# queso_dip_v4_3.net
KiCad netlist of a schematic drawn in EAGLE
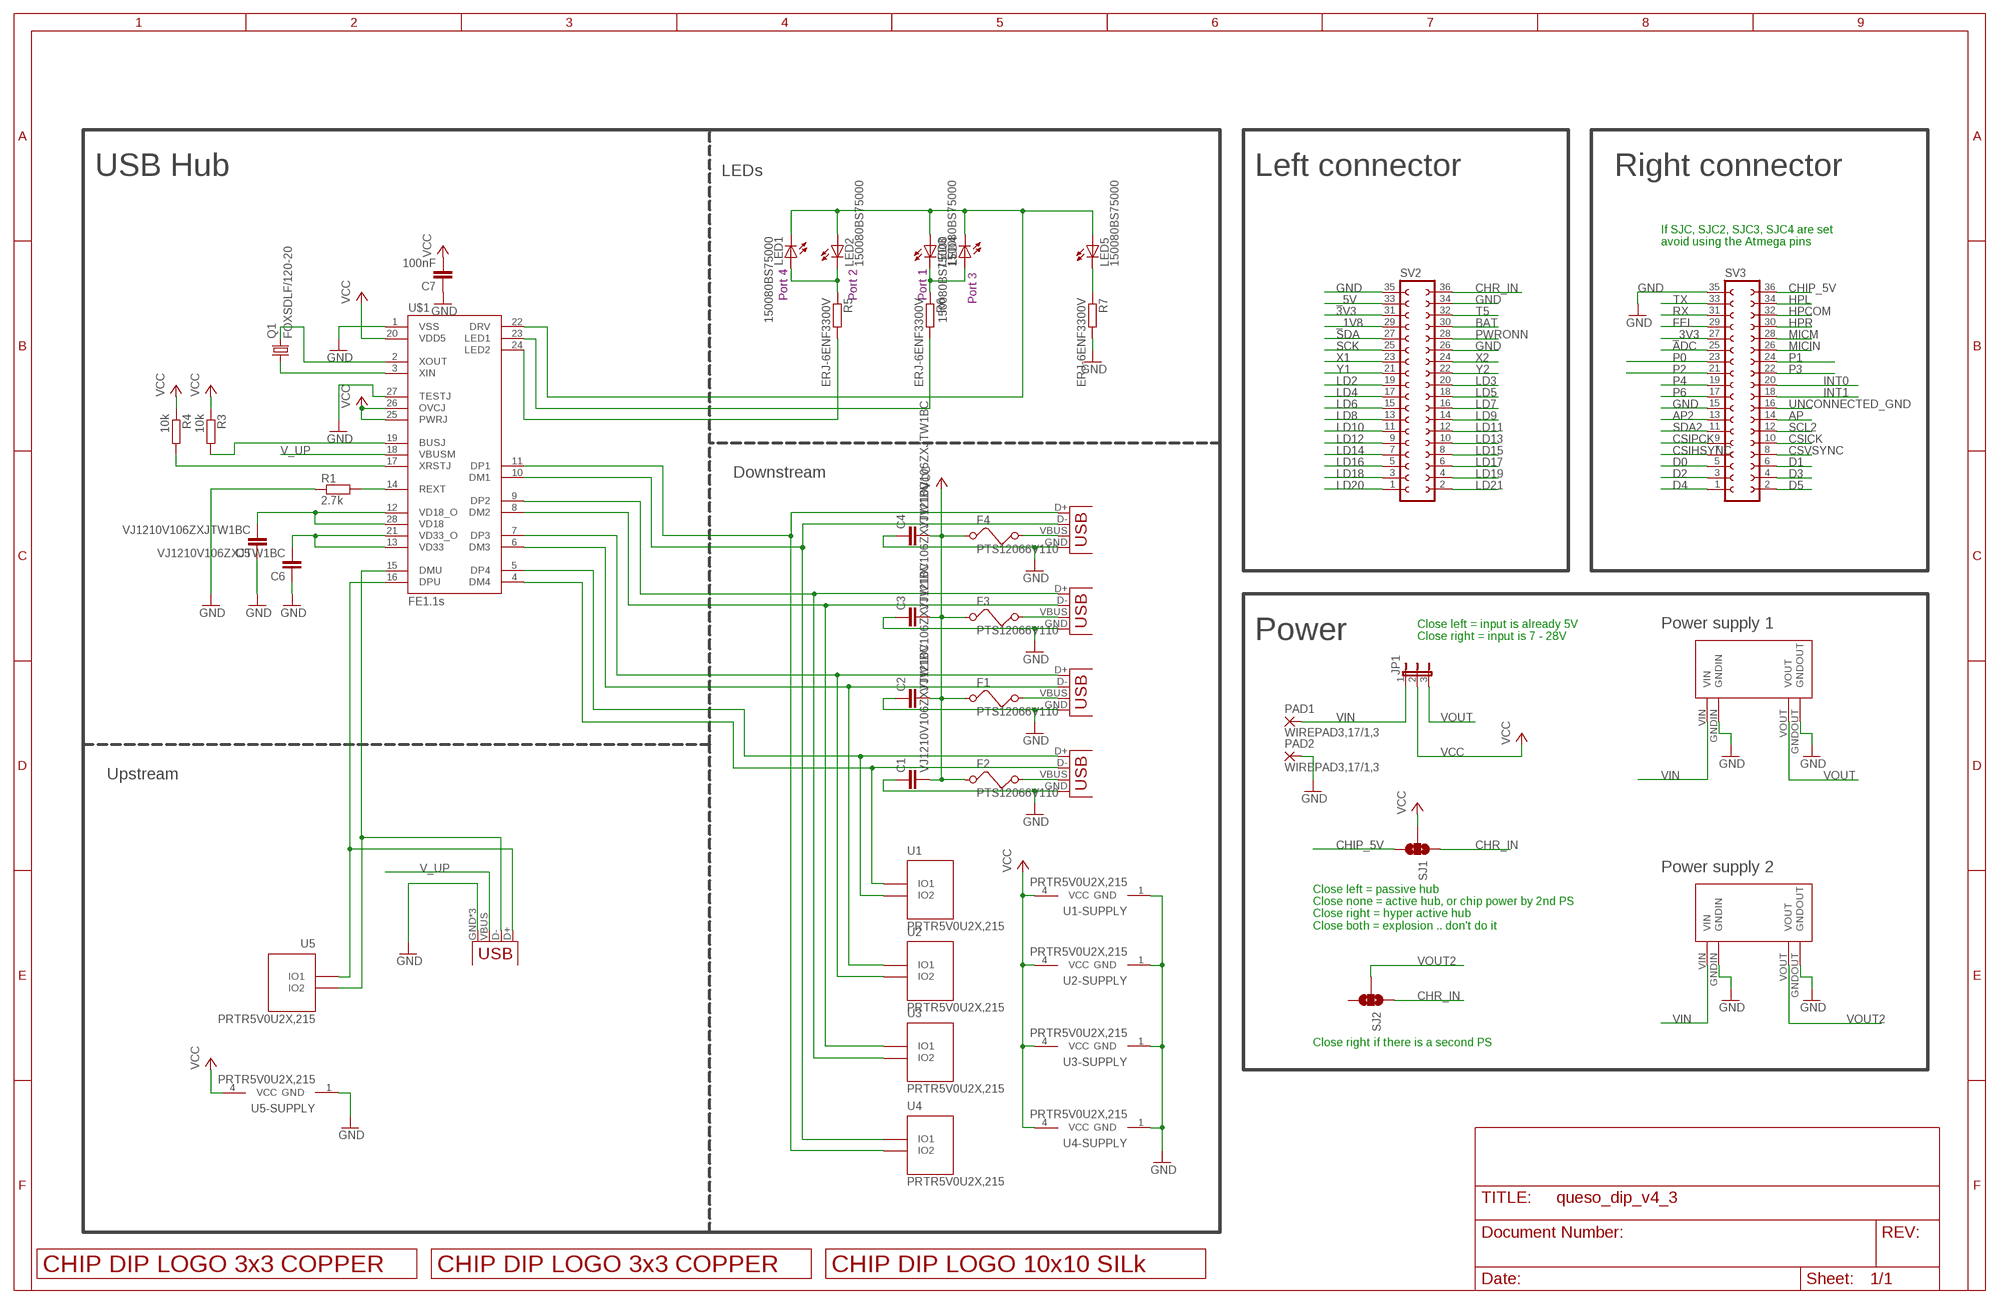
[diagram p0: schematic, sheet 1]

(export (version "E")
  (design (tool "Eeschema 10.0.6"))
  (components
    (comp (ref "C1")
      (value "VJ1210V106ZXJTW1BC")
      (footprint "eagle-import:C1210")
      (libsource (lib "eagle-import") (part "C-EUC1210"))
    )
    (comp (ref "C2")
      (value "VJ1210V106ZXJTW1BC")
      (footprint "eagle-import:C1210")
      (libsource (lib "eagle-import") (part "C-EUC1210"))
    )
    (comp (ref "C3")
      (value "VJ1210V106ZXJTW1BC")
      (footprint "eagle-import:C1210")
      (libsource (lib "eagle-import") (part "C-EUC1210"))
    )
    (comp (ref "C4")
      (value "VJ1210V106ZXJTW1BC")
      (footprint "eagle-import:C1210")
      (libsource (lib "eagle-import") (part "C-EUC1210"))
    )
    (comp (ref "C5")
      (value "VJ1210V106ZXJTW1BC")
      (footprint "eagle-import:C1210")
      (libsource (lib "eagle-import") (part "C-EUC1210"))
    )
    (comp (ref "C6")
      (value "VJ1210V106ZXJTW1BC")
      (footprint "eagle-import:C1210")
      (libsource (lib "eagle-import") (part "C-EUC1210"))
    )
    (comp (ref "C7")
      (value "100nF")
      (footprint "eagle-import:C0805")
      (libsource (lib "eagle-import") (part "C-EUC0805"))
    )
    (comp (ref "F1")
      (value "PTS12066V110")
      (footprint "eagle-import:1210")
      (libsource (lib "eagle-import") (part "FUSED"))
    )
    (comp (ref "F2")
      (value "PTS12066V110")
      (footprint "eagle-import:1210")
      (libsource (lib "eagle-import") (part "FUSED"))
    )
    (comp (ref "F3")
      (value "PTS12066V110")
      (footprint "eagle-import:1210")
      (libsource (lib "eagle-import") (part "FUSED"))
    )
    (comp (ref "F4")
      (value "PTS12066V110")
      (footprint "eagle-import:1210")
      (libsource (lib "eagle-import") (part "FUSED"))
    )
    (comp (ref "JP1")
      (value "JP2E")
      (footprint "eagle-import:JP2")
      (libsource (lib "eagle-import") (part "JP2E"))
    )
    (comp (ref "LED1")
      (value "150080BS75000")
      (footprint "eagle-import:CHIP-LED0805")
      (libsource (lib "eagle-import") (part "LEDCHIP-LED0805"))
    )
    (comp (ref "LED2")
      (value "150080BS75000")
      (footprint "eagle-import:CHIP-LED0805")
      (libsource (lib "eagle-import") (part "LEDCHIP-LED0805"))
    )
    (comp (ref "LED3")
      (value "150080BS75000")
      (footprint "eagle-import:CHIP-LED0805")
      (libsource (lib "eagle-import") (part "LEDCHIP-LED0805"))
    )
    (comp (ref "LED4")
      (value "150080BS75000")
      (footprint "eagle-import:CHIP-LED0805")
      (libsource (lib "eagle-import") (part "LEDCHIP-LED0805"))
    )
    (comp (ref "LED5")
      (value "150080BS75000")
      (footprint "eagle-import:CHIP-LED0805")
      (libsource (lib "eagle-import") (part "LEDCHIP-LED0805"))
    )
    (comp (ref "PAD1")
      (value "WIREPAD3,17/1,3")
      (footprint "eagle-import:3,17_1,3")
      (libsource (lib "eagle-import") (part "WIREPAD3,17/1,3"))
    )
    (comp (ref "PAD2")
      (value "WIREPAD3,17/1,3")
      (footprint "eagle-import:3,17_1,3")
      (libsource (lib "eagle-import") (part "WIREPAD3,17/1,3"))
    )
    (comp (ref "Q1")
      (value "FOXSDLF/120-20")
      (footprint "eagle-import:SM49")
      (libsource (lib "eagle-import") (part "CRYSTALSM49"))
    )
    (comp (ref "R1")
      (value "2.7k")
      (footprint "eagle-import:R0805")
      (libsource (lib "eagle-import") (part "R-EU_R0805"))
    )
    (comp (ref "R3")
      (value "10k")
      (footprint "eagle-import:R0805")
      (libsource (lib "eagle-import") (part "R-EU_R0805"))
    )
    (comp (ref "R4")
      (value "10k")
      (footprint "eagle-import:R0805")
      (libsource (lib "eagle-import") (part "R-EU_R0805"))
    )
    (comp (ref "R5")
      (value "ERJ-6ENF3300V")
      (footprint "eagle-import:R0805")
      (libsource (lib "eagle-import") (part "R-EU_R0805"))
    )
    (comp (ref "R6")
      (value "ERJ-6ENF3300V")
      (footprint "eagle-import:R0805")
      (libsource (lib "eagle-import") (part "R-EU_R0805"))
    )
    (comp (ref "R7")
      (value "ERJ-6ENF3300V")
      (footprint "eagle-import:R0805")
      (libsource (lib "eagle-import") (part "R-EU_R0805"))
    )
    (comp (ref "SJ1")
      (value "SOLDERJUMPER_2WAYT")
      (footprint "eagle-import:SJ_2")
      (libsource (lib "eagle-import") (part "SOLDERJUMPER_2WAYT"))
    )
    (comp (ref "SJ2")
      (value "SOLDERJUMPER_2WAYT")
      (footprint "eagle-import:SJ_2")
      (libsource (lib "eagle-import") (part "SOLDERJUMPER_2WAYT"))
    )
    (comp (ref "SV2")
      (value "FE18-2")
      (footprint "eagle-import:FE18-2")
      (libsource (lib "eagle-import") (part "FE18-2"))
    )
    (comp (ref "SV3")
      (value "FE18-2")
      (footprint "eagle-import:FE18-2")
      (libsource (lib "eagle-import") (part "FE18-2"))
    )
    (comp (ref "U$1")
      (value "FE1.1S")
      (footprint "eagle-import:FE1.1S_SSOP-28")
      (libsource (lib "eagle-import") (part "FE1.1S"))
    )
    (comp (ref "U$2")
      (value "LOGO_3X3_COPPER")
      (footprint "eagle-import:LOGO_3X3_COPPER")
      (libsource (lib "eagle-import") (part "LOGO_3X3_COPPER"))
    )
    (comp (ref "U$3")
      (value "MP1584EN")
      (footprint "eagle-import:MP1584EN")
      (libsource (lib "eagle-import") (part "MP1584EN"))
    )
    (comp (ref "U$4")
      (value "LOGO_3X3_COPPER")
      (footprint "eagle-import:LOGO_3X3_COPPER")
      (libsource (lib "eagle-import") (part "LOGO_3X3_COPPER"))
    )
    (comp (ref "U$5")
      (value "LOGO_10X10_SILK")
      (footprint "eagle-import:LOGO_10X10_SILK")
      (libsource (lib "eagle-import") (part "LOGO_10X10_SILK"))
    )
    (comp (ref "U$9")
      (value "MP1584EN")
      (footprint "eagle-import:MP1584EN")
      (libsource (lib "eagle-import") (part "MP1584EN"))
    )
    (comp (ref "U1")
      (value "PRTR5V0U2X,215")
      (footprint "eagle-import:SOT-143B")
      (fields (field (name "MANUFACTURER") "NXP Semiconductors"))
      (libsource (lib "eagle-import") (part "PRTR5V0U2X?"))
    )
    (comp (ref "U2")
      (value "PRTR5V0U2X,215")
      (footprint "eagle-import:SOT-143B")
      (fields (field (name "MANUFACTURER") "NXP Semiconductors"))
      (libsource (lib "eagle-import") (part "PRTR5V0U2X?"))
    )
    (comp (ref "U3")
      (value "PRTR5V0U2X,215")
      (footprint "eagle-import:SOT-143B")
      (fields (field (name "MANUFACTURER") "NXP Semiconductors"))
      (libsource (lib "eagle-import") (part "PRTR5V0U2X?"))
    )
    (comp (ref "U4")
      (value "PRTR5V0U2X,215")
      (footprint "eagle-import:SOT-143B")
      (fields (field (name "MANUFACTURER") "NXP Semiconductors"))
      (libsource (lib "eagle-import") (part "PRTR5V0U2X?"))
    )
    (comp (ref "U5")
      (value "PRTR5V0U2X,215")
      (footprint "eagle-import:SOT-143B")
      (fields (field (name "MANUFACTURER") "NXP Semiconductors"))
      (libsource (lib "eagle-import") (part "PRTR5V0U2X?"))
    )
    (comp (ref "USB")
      (value "USBUSB-MICROB-SMT-DIP")
      (footprint "eagle-import:USB-MICROB-SMT-DIP")
      (libsource (lib "eagle-import") (part "USBUSB-MICROB-SMT-DIP"))
    )
    (comp (ref "X1")
      (value "USB-A-HU")
      (footprint "eagle-import:USB-A-HU")
      (libsource (lib "eagle-import") (part "USB-A-HU"))
    )
    (comp (ref "X2")
      (value "USB-A-HU")
      (footprint "eagle-import:USB-A-HU")
      (libsource (lib "eagle-import") (part "USB-A-HU"))
    )
    (comp (ref "X3")
      (value "USB-A-HU")
      (footprint "eagle-import:USB-A-HU")
      (libsource (lib "eagle-import") (part "USB-A-HU"))
    )
    (comp (ref "X4")
      (value "USB-A-HU")
      (footprint "eagle-import:USB-A-HU")
      (libsource (lib "eagle-import") (part "USB-A-HU"))
    )
  )
  (nets
    (net (code "1") (name "/3V3") (class "Default")
      (node (ref "SV2") (pin "31") (pinfunction "31_31") (pintype "passive"))
    )
    (net (code "2") (name "/ADC") (class "Default")
      (node (ref "SV3") (pin "25") (pinfunction "25_25") (pintype "passive"))
    )
    (net (code "3") (name "/AP") (class "Default")
      (node (ref "SV3") (pin "14") (pinfunction "14_14") (pintype "passive"))
    )
    (net (code "4") (name "/AP2") (class "Default")
      (node (ref "SV3") (pin "13") (pinfunction "13_13") (pintype "passive"))
    )
    (net (code "5") (name "/BAT") (class "Default")
      (node (ref "SV2") (pin "30") (pinfunction "30_30") (pintype "passive"))
    )
    (net (code "6") (name "/CHIP_5V") (class "Default")
      (node (ref "SJ1") (pin "3") (pinfunction "3_3") (pintype "passive"))
      (node (ref "SV3") (pin "36") (pinfunction "36_36") (pintype "passive"))
    )
    (net (code "7") (name "/CHR_IN") (class "Default")
      (node (ref "SJ1") (pin "1") (pinfunction "1_1") (pintype "passive"))
      (node (ref "SJ2") (pin "1") (pinfunction "1_1") (pintype "passive"))
      (node (ref "SV2") (pin "36") (pinfunction "36_36") (pintype "passive"))
    )
    (net (code "8") (name "/CSICK") (class "Default")
      (node (ref "SV3") (pin "10") (pinfunction "10_10") (pintype "passive"))
    )
    (net (code "9") (name "/CSIHSYNC") (class "Default")
      (node (ref "SV3") (pin "7") (pinfunction "7_7") (pintype "passive"))
    )
    (net (code "10") (name "/CSIPCK") (class "Default")
      (node (ref "SV3") (pin "9") (pinfunction "9_9") (pintype "passive"))
    )
    (net (code "11") (name "/CSVSYNC") (class "Default")
      (node (ref "SV3") (pin "8") (pinfunction "8_8") (pintype "passive"))
    )
    (net (code "12") (name "/D0") (class "Default")
      (node (ref "SV3") (pin "5") (pinfunction "5_5") (pintype "passive"))
    )
    (net (code "13") (name "/D1") (class "Default")
      (node (ref "SV3") (pin "6") (pinfunction "6_6") (pintype "passive"))
    )
    (net (code "14") (name "/D2") (class "Default")
      (node (ref "SV3") (pin "3") (pinfunction "3_3") (pintype "passive"))
    )
    (net (code "15") (name "/D3") (class "Default")
      (node (ref "SV3") (pin "4") (pinfunction "4_4") (pintype "passive"))
    )
    (net (code "16") (name "/D4") (class "Default")
      (node (ref "SV3") (pin "1") (pinfunction "1_1") (pintype "passive"))
    )
    (net (code "17") (name "/D5") (class "Default")
      (node (ref "SV3") (pin "2") (pinfunction "2_2") (pintype "passive"))
    )
    (net (code "18") (name "/FEL") (class "Default")
      (node (ref "SV3") (pin "29") (pinfunction "29_29") (pintype "passive"))
    )
    (net (code "19") (name "/HPCOM") (class "Default")
      (node (ref "SV3") (pin "32") (pinfunction "32_32") (pintype "passive"))
    )
    (net (code "20") (name "/HPL") (class "Default")
      (node (ref "SV3") (pin "34") (pinfunction "34_34") (pintype "passive"))
    )
    (net (code "21") (name "/HPR") (class "Default")
      (node (ref "SV3") (pin "30") (pinfunction "30_30") (pintype "passive"))
    )
    (net (code "22") (name "/INT0") (class "Default")
      (node (ref "SV3") (pin "20") (pinfunction "20_20") (pintype "passive"))
    )
    (net (code "23") (name "/INT1") (class "Default")
      (node (ref "SV3") (pin "18") (pinfunction "18_18") (pintype "passive"))
    )
    (net (code "24") (name "/LD2") (class "Default")
      (node (ref "SV2") (pin "19") (pinfunction "19_19") (pintype "passive"))
    )
    (net (code "25") (name "/LD3") (class "Default")
      (node (ref "SV2") (pin "20") (pinfunction "20_20") (pintype "passive"))
    )
    (net (code "26") (name "/LD4") (class "Default")
      (node (ref "SV2") (pin "17") (pinfunction "17_17") (pintype "passive"))
    )
    (net (code "27") (name "/LD5") (class "Default")
      (node (ref "SV2") (pin "18") (pinfunction "18_18") (pintype "passive"))
    )
    (net (code "28") (name "/LD6") (class "Default")
      (node (ref "SV2") (pin "15") (pinfunction "15_15") (pintype "passive"))
    )
    (net (code "29") (name "/LD7") (class "Default")
      (node (ref "SV2") (pin "16") (pinfunction "16_16") (pintype "passive"))
    )
    (net (code "30") (name "/LD8") (class "Default")
      (node (ref "SV2") (pin "13") (pinfunction "13_13") (pintype "passive"))
    )
    (net (code "31") (name "/LD9") (class "Default")
      (node (ref "SV2") (pin "14") (pinfunction "14_14") (pintype "passive"))
    )
    (net (code "32") (name "/LD10") (class "Default")
      (node (ref "SV2") (pin "11") (pinfunction "11_11") (pintype "passive"))
    )
    (net (code "33") (name "/LD11") (class "Default")
      (node (ref "SV2") (pin "12") (pinfunction "12_12") (pintype "passive"))
    )
    (net (code "34") (name "/LD12") (class "Default")
      (node (ref "SV2") (pin "9") (pinfunction "9_9") (pintype "passive"))
    )
    (net (code "35") (name "/LD13") (class "Default")
      (node (ref "SV2") (pin "10") (pinfunction "10_10") (pintype "passive"))
    )
    (net (code "36") (name "/LD14") (class "Default")
      (node (ref "SV2") (pin "7") (pinfunction "7_7") (pintype "passive"))
    )
    (net (code "37") (name "/LD15") (class "Default")
      (node (ref "SV2") (pin "8") (pinfunction "8_8") (pintype "passive"))
    )
    (net (code "38") (name "/LD16") (class "Default")
      (node (ref "SV2") (pin "5") (pinfunction "5_5") (pintype "passive"))
    )
    (net (code "39") (name "/LD17") (class "Default")
      (node (ref "SV2") (pin "6") (pinfunction "6_6") (pintype "passive"))
    )
    (net (code "40") (name "/LD18") (class "Default")
      (node (ref "SV2") (pin "3") (pinfunction "3_3") (pintype "passive"))
    )
    (net (code "41") (name "/LD19") (class "Default")
      (node (ref "SV2") (pin "4") (pinfunction "4_4") (pintype "passive"))
    )
    (net (code "42") (name "/LD20") (class "Default")
      (node (ref "SV2") (pin "1") (pinfunction "1_1") (pintype "passive"))
    )
    (net (code "43") (name "/LD21") (class "Default")
      (node (ref "SV2") (pin "2") (pinfunction "2_2") (pintype "passive"))
    )
    (net (code "44") (name "/MICIN") (class "Default")
      (node (ref "SV3") (pin "26") (pinfunction "26_26") (pintype "passive"))
    )
    (net (code "45") (name "/MICM") (class "Default")
      (node (ref "SV3") (pin "28") (pinfunction "28_28") (pintype "passive"))
    )
    (net (code "46") (name "/P0") (class "Default")
      (node (ref "SV3") (pin "23") (pinfunction "23_23") (pintype "passive"))
    )
    (net (code "47") (name "/P1") (class "Default")
      (node (ref "SV3") (pin "24") (pinfunction "24_24") (pintype "passive"))
    )
    (net (code "48") (name "/P2") (class "Default")
      (node (ref "SV3") (pin "21") (pinfunction "21_21") (pintype "passive"))
    )
    (net (code "49") (name "/P3") (class "Default")
      (node (ref "SV3") (pin "22") (pinfunction "22_22") (pintype "passive"))
    )
    (net (code "50") (name "/P4") (class "Default")
      (node (ref "SV3") (pin "19") (pinfunction "19_19") (pintype "passive"))
    )
    (net (code "51") (name "/P6") (class "Default")
      (node (ref "SV3") (pin "17") (pinfunction "17_17") (pintype "passive"))
    )
    (net (code "52") (name "/PWRONN") (class "Default")
      (node (ref "SV2") (pin "28") (pinfunction "28_28") (pintype "passive"))
    )
    (net (code "53") (name "/RX") (class "Default")
      (node (ref "SV3") (pin "31") (pinfunction "31_31") (pintype "passive"))
    )
    (net (code "54") (name "/SCK") (class "Default")
      (node (ref "SV2") (pin "25") (pinfunction "25_25") (pintype "passive"))
    )
    (net (code "55") (name "/SCL2") (class "Default")
      (node (ref "SV3") (pin "12") (pinfunction "12_12") (pintype "passive"))
    )
    (net (code "56") (name "/SDA") (class "Default")
      (node (ref "SV2") (pin "27") (pinfunction "27_27") (pintype "passive"))
    )
    (net (code "57") (name "/SDA2") (class "Default")
      (node (ref "SV3") (pin "11") (pinfunction "11_11") (pintype "passive"))
    )
    (net (code "58") (name "/T5") (class "Default")
      (node (ref "SV2") (pin "32") (pinfunction "32_32") (pintype "passive"))
    )
    (net (code "59") (name "/TX") (class "Default")
      (node (ref "SV3") (pin "33") (pinfunction "33_33") (pintype "passive"))
    )
    (net (code "60") (name "/UNCONNECTED_GND") (class "Default")
      (node (ref "SV3") (pin "16") (pinfunction "16_16") (pintype "passive"))
    )
    (net (code "61") (name "/VIN") (class "Default")
      (node (ref "JP1") (pin "1") (pinfunction "1_1") (pintype "passive"))
      (node (ref "PAD1") (pin "1") (pinfunction "P_1") (pintype "passive"))
      (node (ref "U$3") (pin "VIN") (pinfunction "VIN_VIN") (pintype "power_in"))
      (node (ref "U$9") (pin "VIN") (pinfunction "VIN_VIN") (pintype "power_in"))
    )
    (net (code "62") (name "/VOUT") (class "Default")
      (node (ref "JP1") (pin "3") (pinfunction "3_3") (pintype "passive"))
      (node (ref "U$9") (pin "VOUT") (pinfunction "VOUT_VOUT") (pintype "power_in"))
    )
    (net (code "63") (name "/VOUT2") (class "Default")
      (node (ref "SJ2") (pin "2") (pinfunction "2_2") (pintype "passive"))
      (node (ref "U$3") (pin "VOUT") (pinfunction "VOUT_VOUT") (pintype "power_in"))
    )
    (net (code "64") (name "/V_UP") (class "Default")
      (node (ref "U$1") (pin "18") (pinfunction "VBUSM_18") (pintype "bidirectional"))
      (node (ref "USB") (pin "VBUS") (pinfunction "VBUS_VBUS") (pintype "bidirectional"))
    )
    (net (code "65") (name "/X1") (class "Default")
      (node (ref "SV2") (pin "23") (pinfunction "23_23") (pintype "passive"))
    )
    (net (code "66") (name "/X2") (class "Default")
      (node (ref "SV2") (pin "24") (pinfunction "24_24") (pintype "passive"))
    )
    (net (code "67") (name "/Y1") (class "Default")
      (node (ref "SV2") (pin "21") (pinfunction "21_21") (pintype "passive"))
    )
    (net (code "68") (name "/Y2") (class "Default")
      (node (ref "SV2") (pin "22") (pinfunction "22_22") (pintype "passive"))
    )
    (net (code "69") (name "/_1V8") (class "Default")
      (node (ref "SV2") (pin "29") (pinfunction "29_29") (pintype "passive"))
    )
    (net (code "70") (name "/_3V3") (class "Default")
      (node (ref "SV3") (pin "27") (pinfunction "27_27") (pintype "passive"))
    )
    (net (code "71") (name "/_5V") (class "Default")
      (node (ref "SV2") (pin "33") (pinfunction "33_33") (pintype "passive"))
    )
    (net (code "72") (name "GND") (class "Default")
      (node (ref "C1") (pin "1") (pinfunction "1_1") (pintype "passive"))
      (node (ref "C2") (pin "1") (pinfunction "1_1") (pintype "passive"))
      (node (ref "C3") (pin "1") (pinfunction "1_1") (pintype "passive"))
      (node (ref "C4") (pin "1") (pinfunction "1_1") (pintype "passive"))
      (node (ref "C5") (pin "1") (pinfunction "1_1") (pintype "passive"))
      (node (ref "C6") (pin "1") (pinfunction "1_1") (pintype "passive"))
      (node (ref "C7") (pin "1") (pinfunction "1_1") (pintype "passive"))
      (node (ref "PAD2") (pin "1") (pinfunction "P_1") (pintype "passive"))
      (node (ref "R1") (pin "1") (pinfunction "1_1") (pintype "passive"))
      (node (ref "R7") (pin "2") (pinfunction "2_2") (pintype "passive"))
      (node (ref "SV2") (pin "26") (pinfunction "26_26") (pintype "passive"))
      (node (ref "SV2") (pin "34") (pinfunction "34_34") (pintype "passive"))
      (node (ref "SV2") (pin "35") (pinfunction "35_35") (pintype "passive"))
      (node (ref "SV3") (pin "15") (pinfunction "15_15") (pintype "passive"))
      (node (ref "SV3") (pin "35") (pinfunction "35_35") (pintype "passive"))
      (node (ref "U$1") (pin "1") (pinfunction "VSS_1") (pintype "bidirectional"))
      (node (ref "U$1") (pin "27") (pinfunction "TESTJ_27") (pintype "bidirectional"))
      (node (ref "U$3") (pin "GNDIN") (pinfunction "GNDIN_GNDIN") (pintype "power_in"))
      (node (ref "U$3") (pin "GNDOUT") (pinfunction "GNDOUT_GNDOUT") (pintype "power_in"))
      (node (ref "U$9") (pin "GNDIN") (pinfunction "GNDIN_GNDIN") (pintype "power_in"))
      (node (ref "U$9") (pin "GNDOUT") (pinfunction "GNDOUT_GNDOUT") (pintype "power_in"))
      (node (ref "U1") (pin "1") (pinfunction "GND_1") (pintype "bidirectional"))
      (node (ref "U2") (pin "1") (pinfunction "GND_1") (pintype "bidirectional"))
      (node (ref "U3") (pin "1") (pinfunction "GND_1") (pintype "bidirectional"))
      (node (ref "U4") (pin "1") (pinfunction "GND_1") (pintype "bidirectional"))
      (node (ref "U5") (pin "1") (pinfunction "GND_1") (pintype "bidirectional"))
      (node (ref "USB") (pin "GND") (pinfunction "GND_GND") (pintype "bidirectional"))
      (node (ref "USB") (pin "MT1") (pinfunction "GND_MT1") (pintype "bidirectional"))
      (node (ref "USB") (pin "MT2") (pinfunction "GND_MT2") (pintype "bidirectional"))
      (node (ref "X1") (pin "GND") (pinfunction "GND_GND") (pintype "bidirectional"))
      (node (ref "X2") (pin "GND") (pinfunction "GND_GND") (pintype "bidirectional"))
      (node (ref "X3") (pin "GND") (pinfunction "GND_GND") (pintype "bidirectional"))
      (node (ref "X4") (pin "GND") (pinfunction "GND_GND") (pintype "bidirectional"))
    )
    (net (code "73") (name "Net-(F1-Pad2)") (class "Default")
      (node (ref "F1") (pin "2") (pinfunction "2_2") (pintype "passive"))
      (node (ref "X2") (pin "VBUS") (pinfunction "VBUS_VBUS") (pintype "bidirectional"))
    )
    (net (code "74") (name "Net-(F2-Pad2)") (class "Default")
      (node (ref "F2") (pin "2") (pinfunction "2_2") (pintype "passive"))
      (node (ref "X1") (pin "VBUS") (pinfunction "VBUS_VBUS") (pintype "bidirectional"))
    )
    (net (code "75") (name "Net-(F3-Pad2)") (class "Default")
      (node (ref "F3") (pin "2") (pinfunction "2_2") (pintype "passive"))
      (node (ref "X3") (pin "VBUS") (pinfunction "VBUS_VBUS") (pintype "bidirectional"))
    )
    (net (code "76") (name "Net-(F4-Pad2)") (class "Default")
      (node (ref "F4") (pin "2") (pinfunction "2_2") (pintype "passive"))
      (node (ref "X4") (pin "VBUS") (pinfunction "VBUS_VBUS") (pintype "bidirectional"))
    )
    (net (code "77") (name "Net-(LED1-PadA)") (class "Default")
      (node (ref "LED1") (pin "A") (pinfunction "A_A") (pintype "passive"))
      (node (ref "LED2") (pin "C") (pinfunction "C_C") (pintype "passive"))
      (node (ref "R5") (pin "1") (pinfunction "1_1") (pintype "passive"))
    )
    (net (code "78") (name "Net-(LED3-PadC)") (class "Default")
      (node (ref "LED3") (pin "C") (pinfunction "C_C") (pintype "passive"))
      (node (ref "LED4") (pin "A") (pinfunction "A_A") (pintype "passive"))
      (node (ref "R6") (pin "1") (pinfunction "1_1") (pintype "passive"))
    )
    (net (code "79") (name "Net-(LED5-PadC)") (class "Default")
      (node (ref "LED5") (pin "C") (pinfunction "C_C") (pintype "passive"))
      (node (ref "R7") (pin "1") (pinfunction "1_1") (pintype "passive"))
    )
    (net (code "80") (name "Net-(U$1-BUSJ)") (class "Default")
      (node (ref "R3") (pin "2") (pinfunction "2_2") (pintype "passive"))
      (node (ref "U$1") (pin "19") (pinfunction "BUSJ_19") (pintype "bidirectional"))
    )
    (net (code "81") (name "Net-(U$1-DM1)") (class "Default")
      (node (ref "U$1") (pin "10") (pinfunction "DM1_10") (pintype "bidirectional"))
      (node (ref "U4") (pin "2") (pinfunction "IO1_2") (pintype "bidirectional"))
      (node (ref "X4") (pin "D-") (pinfunction "D-_D-") (pintype "bidirectional"))
    )
    (net (code "82") (name "Net-(U$1-DM2)") (class "Default")
      (node (ref "U$1") (pin "8") (pinfunction "DM2_8") (pintype "bidirectional"))
      (node (ref "U3") (pin "2") (pinfunction "IO1_2") (pintype "bidirectional"))
      (node (ref "X3") (pin "D-") (pinfunction "D-_D-") (pintype "bidirectional"))
    )
    (net (code "83") (name "Net-(U$1-DM3)") (class "Default")
      (node (ref "U$1") (pin "6") (pinfunction "DM3_6") (pintype "bidirectional"))
      (node (ref "U2") (pin "2") (pinfunction "IO1_2") (pintype "bidirectional"))
      (node (ref "X2") (pin "D-") (pinfunction "D-_D-") (pintype "bidirectional"))
    )
    (net (code "84") (name "Net-(U$1-DM4)") (class "Default")
      (node (ref "U$1") (pin "4") (pinfunction "DM4_4") (pintype "bidirectional"))
      (node (ref "U1") (pin "2") (pinfunction "IO1_2") (pintype "bidirectional"))
      (node (ref "X1") (pin "D-") (pinfunction "D-_D-") (pintype "bidirectional"))
    )
    (net (code "85") (name "Net-(U$1-DMU)") (class "Default")
      (node (ref "U$1") (pin "15") (pinfunction "DMU_15") (pintype "bidirectional"))
      (node (ref "U5") (pin "3") (pinfunction "IO2_3") (pintype "bidirectional"))
      (node (ref "USB") (pin "D-") (pinfunction "D-_D-") (pintype "bidirectional"))
    )
    (net (code "86") (name "Net-(U$1-DP1)") (class "Default")
      (node (ref "U$1") (pin "11") (pinfunction "DP1_11") (pintype "bidirectional"))
      (node (ref "U4") (pin "3") (pinfunction "IO2_3") (pintype "bidirectional"))
      (node (ref "X4") (pin "D+") (pinfunction "D+_D+") (pintype "bidirectional"))
    )
    (net (code "87") (name "Net-(U$1-DP2)") (class "Default")
      (node (ref "U$1") (pin "9") (pinfunction "DP2_9") (pintype "bidirectional"))
      (node (ref "U3") (pin "3") (pinfunction "IO2_3") (pintype "bidirectional"))
      (node (ref "X3") (pin "D+") (pinfunction "D+_D+") (pintype "bidirectional"))
    )
    (net (code "88") (name "Net-(U$1-DP3)") (class "Default")
      (node (ref "U$1") (pin "7") (pinfunction "DP3_7") (pintype "bidirectional"))
      (node (ref "U2") (pin "3") (pinfunction "IO2_3") (pintype "bidirectional"))
      (node (ref "X2") (pin "D+") (pinfunction "D+_D+") (pintype "bidirectional"))
    )
    (net (code "89") (name "Net-(U$1-DP4)") (class "Default")
      (node (ref "U$1") (pin "5") (pinfunction "DP4_5") (pintype "bidirectional"))
      (node (ref "U1") (pin "3") (pinfunction "IO2_3") (pintype "bidirectional"))
      (node (ref "X1") (pin "D+") (pinfunction "D+_D+") (pintype "bidirectional"))
    )
    (net (code "90") (name "Net-(U$1-DPU)") (class "Default")
      (node (ref "U$1") (pin "16") (pinfunction "DPU_16") (pintype "bidirectional"))
      (node (ref "U5") (pin "2") (pinfunction "IO1_2") (pintype "bidirectional"))
      (node (ref "USB") (pin "D+") (pinfunction "D+_D+") (pintype "bidirectional"))
    )
    (net (code "91") (name "Net-(U$1-DRV)") (class "Default")
      (node (ref "LED1") (pin "C") (pinfunction "C_C") (pintype "passive"))
      (node (ref "LED2") (pin "A") (pinfunction "A_A") (pintype "passive"))
      (node (ref "LED3") (pin "A") (pinfunction "A_A") (pintype "passive"))
      (node (ref "LED4") (pin "C") (pinfunction "C_C") (pintype "passive"))
      (node (ref "LED5") (pin "A") (pinfunction "A_A") (pintype "passive"))
      (node (ref "U$1") (pin "22") (pinfunction "DRV_22") (pintype "bidirectional"))
    )
    (net (code "92") (name "Net-(U$1-LED1)") (class "Default")
      (node (ref "R6") (pin "2") (pinfunction "2_2") (pintype "passive"))
      (node (ref "U$1") (pin "23") (pinfunction "LED1_23") (pintype "bidirectional"))
    )
    (net (code "93") (name "Net-(U$1-LED2)") (class "Default")
      (node (ref "R5") (pin "2") (pinfunction "2_2") (pintype "passive"))
      (node (ref "U$1") (pin "24") (pinfunction "LED2_24") (pintype "bidirectional"))
    )
    (net (code "94") (name "Net-(U$1-REXT)") (class "Default")
      (node (ref "R1") (pin "2") (pinfunction "2_2") (pintype "passive"))
      (node (ref "U$1") (pin "14") (pinfunction "REXT_14") (pintype "bidirectional"))
    )
    (net (code "95") (name "Net-(U$1-VD18)") (class "Default")
      (node (ref "C5") (pin "2") (pinfunction "2_2") (pintype "passive"))
      (node (ref "U$1") (pin "12") (pinfunction "VD18_O_12") (pintype "bidirectional"))
      (node (ref "U$1") (pin "28") (pinfunction "VD18_28") (pintype "bidirectional"))
    )
    (net (code "96") (name "Net-(U$1-VD33)") (class "Default")
      (node (ref "C6") (pin "2") (pinfunction "2_2") (pintype "passive"))
      (node (ref "U$1") (pin "13") (pinfunction "VD33_13") (pintype "bidirectional"))
      (node (ref "U$1") (pin "21") (pinfunction "VD33_O_21") (pintype "bidirectional"))
    )
    (net (code "97") (name "Net-(U$1-XIN)") (class "Default")
      (node (ref "Q1") (pin "1") (pinfunction "1_1") (pintype "passive"))
      (node (ref "U$1") (pin "3") (pinfunction "XIN_3") (pintype "bidirectional"))
    )
    (net (code "98") (name "Net-(U$1-XOUT)") (class "Default")
      (node (ref "Q1") (pin "2") (pinfunction "2_2") (pintype "passive"))
      (node (ref "U$1") (pin "2") (pinfunction "XOUT_2") (pintype "bidirectional"))
    )
    (net (code "99") (name "Net-(U$1-XRSTJ)") (class "Default")
      (node (ref "R4") (pin "2") (pinfunction "2_2") (pintype "passive"))
      (node (ref "U$1") (pin "17") (pinfunction "XRSTJ_17") (pintype "bidirectional"))
    )
    (net (code "100") (name "VCC") (class "Default")
      (node (ref "C1") (pin "2") (pinfunction "2_2") (pintype "passive"))
      (node (ref "C2") (pin "2") (pinfunction "2_2") (pintype "passive"))
      (node (ref "C3") (pin "2") (pinfunction "2_2") (pintype "passive"))
      (node (ref "C4") (pin "2") (pinfunction "2_2") (pintype "passive"))
      (node (ref "C7") (pin "2") (pinfunction "2_2") (pintype "passive"))
      (node (ref "F1") (pin "1") (pinfunction "1_1") (pintype "passive"))
      (node (ref "F2") (pin "1") (pinfunction "1_1") (pintype "passive"))
      (node (ref "F3") (pin "1") (pinfunction "1_1") (pintype "passive"))
      (node (ref "F4") (pin "1") (pinfunction "1_1") (pintype "passive"))
      (node (ref "JP1") (pin "2") (pinfunction "2_2") (pintype "passive"))
      (node (ref "R3") (pin "1") (pinfunction "1_1") (pintype "passive"))
      (node (ref "R4") (pin "1") (pinfunction "1_1") (pintype "passive"))
      (node (ref "SJ1") (pin "2") (pinfunction "2_2") (pintype "passive"))
      (node (ref "U$1") (pin "20") (pinfunction "VDD5_20") (pintype "bidirectional"))
      (node (ref "U$1") (pin "25") (pinfunction "PWRJ_25") (pintype "bidirectional"))
      (node (ref "U$1") (pin "26") (pinfunction "OVCJ_26") (pintype "bidirectional"))
      (node (ref "U1") (pin "4") (pinfunction "VCC_4") (pintype "bidirectional"))
      (node (ref "U2") (pin "4") (pinfunction "VCC_4") (pintype "bidirectional"))
      (node (ref "U3") (pin "4") (pinfunction "VCC_4") (pintype "bidirectional"))
      (node (ref "U4") (pin "4") (pinfunction "VCC_4") (pintype "bidirectional"))
      (node (ref "U5") (pin "4") (pinfunction "VCC_4") (pintype "bidirectional"))
    )
    (net (code "101") (name "unconnected-(SJ2-Pad3)") (class "Default")
      (node (ref "SJ2") (pin "3") (pinfunction "3_3") (pintype "passive"))
    )
  )
)
